# Motor_Interface_-_Pre-Charge_Logic.net
KiCad netlist of a schematic drawn in Altium Designer
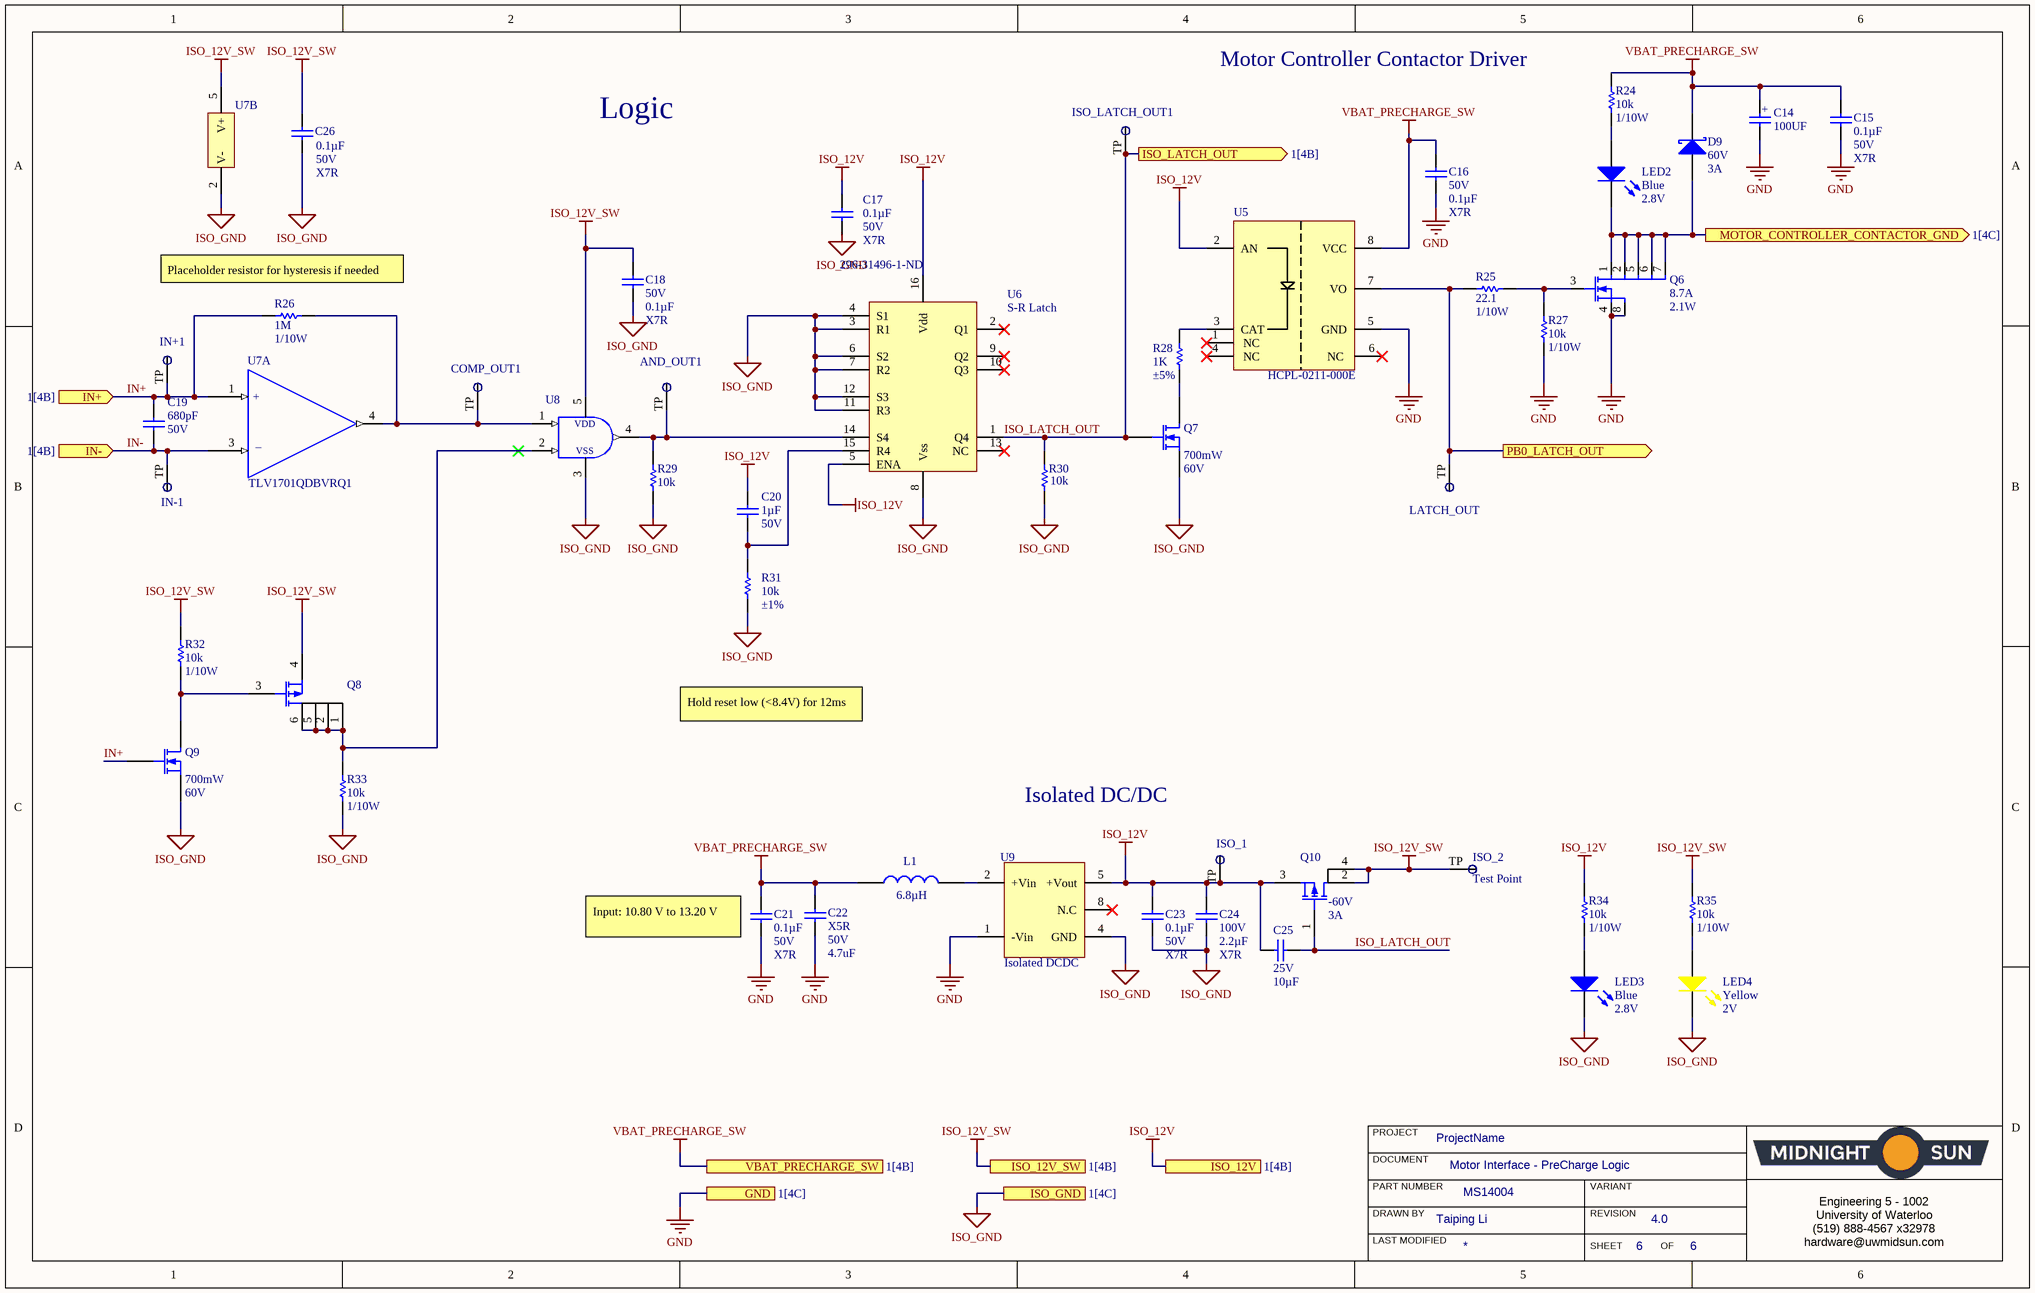
[diagram p0: Motor Interface - Pre-Charge Logic.SchDoc]

(export (version "E")
  (design (tool "Eeschema 10.0.6"))
  (components
    (comp (ref "AND_OUT1")
      (value "Test Point")
      (footprint "Test Point")
      (libsource (lib "Schematic Diagrams") (part "Test Point"))
    )
    (comp (ref "C14")
      (value "100UF")
      (footprint "CAP ALUM 6.3MM RADIAL SMD")
      (description "100µF 35V Aluminum Electrolytic Capacitors Radial, Can - SMD 2000 Hrs @ 85°C")
      (fields (field (name "TOLERANCE") "20%") (field (name "VOLTAGE") "35V"))
      (libsource (lib "altium-import") (part "root_0_CAP ALUM 100UF 20% 35V SMD_"))
    )
    (comp (ref "C15")
      (value "CAP CER 0.1UF 50V 10% X7R 0603")
      (footprint "CAP, 0603")
      (description "0.10µF ±10% 50V Ceramic Capacitor X7R 0603 (1608 Metric)")
      (fields
        (field (name "TOLERANCE") "±10%")
        (field (name "CAPACITANCE") "0.1µF")
        (field (name "VOLTAGE") "50V")
        (field (name "TEMPERATURE COEFFICIENT") "X7R")
      )
      (libsource (lib "Schematic Diagrams") (part "CAP CER 0.1UF 50V 10% X7R 0603"))
    )
    (comp (ref "C16")
      (value "CAP CER 0.1UF 50V 10% X7R 0603")
      (footprint "CAP, 0603")
      (description "0.10µF ±10% 50V Ceramic Capacitor X7R 0603 (1608 Metric)")
      (fields
        (field (name "VOLTAGE") "50V")
        (field (name "TOLERANCE") "±10%")
        (field (name "CAPACITANCE") "0.1µF")
        (field (name "TEMPERATURE COEFFICIENT") "X7R")
      )
      (libsource (lib "Schematic Diagrams") (part "CAP CER 0.1UF 50V 10% X7R 0603"))
    )
    (comp (ref "C17")
      (value "CAP CER 0.1UF 50V 10% X7R 0603")
      (footprint "CAP, 0603")
      (description "0.10µF ±10% 50V Ceramic Capacitor X7R 0603 (1608 Metric)")
      (fields
        (field (name "VOLTAGE") "50V")
        (field (name "TOLERANCE") "±10%")
        (field (name "CAPACITANCE") "0.1µF")
        (field (name "TEMPERATURE COEFFICIENT") "X7R")
      )
      (libsource (lib "Schematic Diagrams") (part "CAP CER 0.1UF 50V 10% X7R 0603"))
    )
    (comp (ref "C18")
      (value "CAP CER 0.1UF 50V 10% X7R 0603")
      (footprint "CAP, 0603")
      (description "0.10µF ±10% 50V Ceramic Capacitor X7R 0603 (1608 Metric)")
      (fields
        (field (name "VOLTAGE") "50V")
        (field (name "TOLERANCE") "±10%")
        (field (name "CAPACITANCE") "0.1µF")
        (field (name "TEMPERATURE COEFFICIENT") "X7R")
      )
      (libsource (lib "Schematic Diagrams") (part "CAP CER 0.1UF 50V 10% X7R 0603"))
    )
    (comp (ref "C19")
      (value "CAP CER 680PF 50V C0G/NP0 0603")
      (footprint "CAP, 0603")
      (description "680pF ±5% 50V Ceramic Capacitor C0G, NP0 0603 (1608 Metric)")
      (fields
        (field (name "MANUFACTURER") "Samsung")
        (field (name "MANUFACTURER PART NUMBER") "CL10C681JB8NNNC")
        (field (name "VOLTAGE") "50V")
        (field (name "CAPACITANCE") "680pF")
      )
      (libsource (lib "Schematic Diagrams") (part "CAP CER 680PF 50V C0G 0603"))
    )
    (comp (ref "C20")
      (value "CAP CER 1UF 50V 10% X7R 0603")
      (footprint "CAP, 0603")
      (description "1µF ±10% 50V Ceramic Capacitor X7R 0603 (1608 Metric)")
      (fields
        (field (name "VOLTAGE") "50V")
        (field (name "TOLERANCE") "±10%")
        (field (name "CAPACITANCE") "1µF")
      )
      (libsource (lib "Schematic Diagrams") (part "CAP CER 1UF 50V 10% X7R 0603"))
    )
    (comp (ref "C21")
      (value "CAP CER 0.1UF 50V 10% X7R 0603")
      (footprint "CAP, 0603")
      (description "0.10µF ±10% 50V Ceramic Capacitor X7R 0603 (1608 Metric)")
      (fields
        (field (name "TOLERANCE") "±10%")
        (field (name "CAPACITANCE") "0.1µF")
        (field (name "VOLTAGE") "50V")
        (field (name "TEMPERATURE COEFFICIENT") "X7R")
      )
      (libsource (lib "altium-import") (part "root_0_CAP CER 0.1UF 50V 10% X7R 0603_"))
    )
    (comp (ref "C22")
      (value "4.7uF")
      (footprint "CAP, 0805")
      (description "4.7µF ±20% 50V Ceramic Capacitor X5R 0805 (2012 Metric)")
      (fields
        (field (name "TOLERANCE") "±20%")
        (field (name "TEMPERATURE COEFFICIENT") "X5R")
        (field (name "VOLTAGE - RATED") "50V")
        (field (name "Comment") "CAP CER 4.7UF 50V 10% X5R 0805")
      )
      (libsource (lib "Schematic Diagrams") (part "CAP CER 4.7UF 50V 10% X5R 0805"))
    )
    (comp (ref "C23")
      (value "CAP CER 0.1UF 50V 10% X7R 0603")
      (footprint "CAP, 0603")
      (description "0.10µF ±10% 50V Ceramic Capacitor X7R 0603 (1608 Metric)")
      (fields
        (field (name "TOLERANCE") "±10%")
        (field (name "CAPACITANCE") "0.1µF")
        (field (name "VOLTAGE") "50V")
        (field (name "TEMPERATURE COEFFICIENT") "X7R")
      )
      (libsource (lib "altium-import") (part "root_0_CAP CER 0.1UF 50V 10% X7R 0603_"))
    )
    (comp (ref "C24")
      (value "CAP CER 2.2UF 100V ±20% X7R 1206")
      (footprint "CAP, 1206")
      (description "2.2µF ±20% 100V Ceramic Capacitor X7R 1206 (3216 Metric)")
      (fields
        (field (name "VOLTAGE") "100V")
        (field (name "TOLERANCE") "±20%")
        (field (name "CAPACITANCE") "2.2µF")
        (field (name "TEMPERATURE COEFFICIENT") "X7R")
      )
      (libsource (lib "Schematic Diagrams") (part "CAP CER 2.2UF 100V ±20% X7R 1206"))
    )
    (comp (ref "C25")
      (value "CAP CER 10uF 25V 10% X5R 0805")
      (footprint "CAP, 0805")
      (description "10µF ±10% 25V Ceramic Capacitor X5R 0805 (2012 Metric)")
      (fields
        (field (name "MANUFACTURER") "Murata Electronics North America")
        (field (name "MANUFACTURER PART NUMBER") "GRM21BR61E106KA73L")
        (field (name "VOLTAGE - RATED") "25V")
        (field (name "CAPACITANCE") "10µF")
      )
      (libsource (lib "Schematic Diagrams") (part "CAP CER 10uF 25V 10% X5R 0805"))
    )
    (comp (ref "C26")
      (value "CAP CER 0.1UF 50V 10% X7R 0603")
      (footprint "CAP, 0603")
      (description "0.10µF ±10% 50V Ceramic Capacitor X7R 0603 (1608 Metric)")
      (fields
        (field (name "VOLTAGE") "50V")
        (field (name "TOLERANCE") "±10%")
        (field (name "CAPACITANCE") "0.1µF")
        (field (name "TEMPERATURE COEFFICIENT") "X7R")
      )
      (libsource (lib "Schematic Diagrams") (part "CAP CER 0.1UF 50V 10% X7R 0603"))
    )
    (comp (ref "COMP_OUT1")
      (value "Test Point")
      (footprint "Test Point")
      (libsource (lib "Schematic Diagrams") (part "Test Point"))
    )
    (comp (ref "D9")
      (value "DIODE SCHOTTKY 60V 3A SMA")
      (footprint "Diode, SMA")
      (description "Diode Schottky 60V 3A Surface Mount SMA")
      (fields
        (field (name "VOLTAGE - DC REVERSE (VR) (MAX)") "60V")
        (field (name "CURRENT - AVERAGE RECTIFIED (IO)") "3A")
      )
      (libsource (lib "Schematic Diagrams") (part "DIODE SCHOTTKY 60V 3A SMA"))
    )
    (comp (ref "IN+1")
      (value "Test Point")
      (footprint "Test Point")
      (libsource (lib "Schematic Diagrams") (part "Test Point"))
    )
    (comp (ref "IN-1")
      (value "Test Point")
      (footprint "Test Point")
      (libsource (lib "Schematic Diagrams") (part "Test Point"))
    )
    (comp (ref "ISO_1")
      (value "Test Point")
      (footprint "Test Point")
      (libsource (lib "Schematic Diagrams") (part "Test Point"))
    )
    (comp (ref "ISO_2")
      (value "Test Point")
      (footprint "Test Point")
      (libsource (lib "Schematic Diagrams") (part "Test Point"))
    )
    (comp (ref "ISO_LATCH_OUT1")
      (value "Test Point")
      (footprint "Test Point")
      (libsource (lib "Schematic Diagrams") (part "Test Point"))
    )
    (comp (ref "L1")
      (value "IND 6.8uH 260mA 20% 1210")
      (footprint "NLFV32T-6R8M-EF/IND 6.8uH")
      (description "6.8µH Shielded Wirewound Inductor 260mA 204 mOhm Max 1210 (3225 Metric)")
      (fields (field (name "TOLERANCE") "±20%") (field (name "INDUCTANCE") "6.8µH"))
      (libsource (lib "Schematic Diagrams") (part "IND 6.8uH 260mA 20% 1210"))
    )
    (comp (ref "LATCH_OUT")
      (value "Test Point")
      (footprint "Test Point")
      (libsource (lib "Schematic Diagrams") (part "Test Point"))
    )
    (comp (ref "LED2")
      (value "LED BLUE CLEAR 2.8V 0603")
      (footprint "LED_0603")
      (description "Blue 470nm LED Indication - Discrete 2.8V 0603 (1608 Metric)")
      (fields (field (name "COLOR") "Blue") (field (name "VOLTAGE - FORWARD (VF) (TYP)") "2.8V"))
      (libsource (lib "altium-import") (part "root_3_LED BLUE CLEAR 2.8V 0603_"))
    )
    (comp (ref "LED3")
      (value "LED BLUE CLEAR 2.8V 0603")
      (footprint "LED_0603")
      (description "Blue 470nm LED Indication - Discrete 2.8V 0603 (1608 Metric)")
      (fields (field (name "COLOR") "Blue") (field (name "VOLTAGE - FORWARD (VF) (TYP)") "2.8V"))
      (libsource (lib "Schematic Diagrams") (part "LED BLUE CLEAR 2.8V 0603"))
    )
    (comp (ref "LED4")
      (value "LED YELLOW CLEAR 2.1V 0603")
      (footprint "LED_0603")
      (description "Yellow 590nm LED Indication - Discrete 2V 0603 (1608 Metric)")
      (fields
        (field (name "MANUFACTURER") "Wurth Electronics Inc.")
        (field (name "MANUFACTURER PART NUMBER") "150060YS75000")
        (field (name "COLOR") "Yellow")
        (field (name "VOLTAGE - FORWARD (VF) (TYP)") "2V")
      )
      (libsource (lib "Schematic Diagrams") (part "LED YELLOW CLEAR 2.1V 0603"))
    )
    (comp (ref "Q6")
      (value "MOSFET N-CH 30V 8.7A 2.1W 6-PQFN (2x2)")
      (footprint "MOSFET N-CH 30V 12A 2mmx2mm PQFN")
      (fields
        (field (name "CURRENT - CONTINUOUS DRAIN (ID) @ 25°C") "8.7A")
        (field (name "POWER DISSIPATION (MAX)") "2.1W")
      )
      (libsource (lib "altium-import") (part "root_0_MOSFET N-CH 30V 8.7A 2.1W 6-PQFN (2x2)_"))
    )
    (comp (ref "Q7")
      (value "MOSFET N-CH 60V 310MA SOT23")
      (footprint "SOT23")
      (description "N-Channel 60V 310mA (Ta) 370mW (Ta) Surface Mount SOT-23")
      (fields
        (field (name "MANUFACTURER") "Diodes")
        (field (name "MANUFACTURER PART NUMBER") "DMN6140L-7")
        (field (name "MAX POWER DISSIPATION") "700mW")
        (field (name "DRAIN TO SOURCE VOLTAGE (VDSS)") "60V")
      )
      (libsource (lib "Schematic Diagrams") (part "MOSFET N-CH 60V 310MA SOT23"))
    )
    (comp (ref "Q8")
      (value "MOSFET P-CH 30V 4A 1.6W SOT-23-6")
      (footprint "P-MOSFET")
      (description "P-Channel 30V 4A (Ta) 1.6W (Ta) Surface Mount SOT-23-6")
      (libsource (lib "Schematic Diagrams") (part "MOSFET P-CH 30V 4A 1.6W SOT-23-6"))
    )
    (comp (ref "Q9")
      (value "MOSFET N-CH 60V 310MA SOT23")
      (footprint "SOT23")
      (description "N-Channel 60V 310mA (Ta) 370mW (Ta) Surface Mount SOT-23")
      (fields
        (field (name "MANUFACTURER") "Diodes")
        (field (name "MANUFACTURER PART NUMBER") "DMN6140L-7")
        (field (name "MAX POWER DISSIPATION") "700mW")
        (field (name "DRAIN TO SOURCE VOLTAGE (VDSS)") "60V")
      )
      (libsource (lib "Schematic Diagrams") (part "MOSFET N-CH 60V 310MA SOT23"))
    )
    (comp (ref "Q10")
      (value "P-Channel")
      (footprint "SOT223_N")
      (description "P-Channel 60V 3A (Ta) 2W (Ta) Surface Mount SOT-223")
      (fields
        (field (name "MANUFACTURER") "Diodes")
        (field (name "MANUFACTURER PART NUMBER") "ZXMP6A17GQTA")
        (field (name "CONTINUOUS DRAIN CURRENT (ID)") "3A")
        (field (name "DRAIN TO SOURCE BREAKDOWN VOLTAGE") "-60V")
      )
      (libsource (lib "Schematic Diagrams") (part "MOSFET P-CH 60V 3A SOT223"))
    )
    (comp (ref "R24")
      (value "RES 10K OHM 1% 1/10W 0603")
      (footprint "RES, 0603")
      (description "RES SMD 10K OHM 1% 1/10W 0603")
      (fields
        (field (name "TOLERANCE") "±1%")
        (field (name "RESISTANCE") "10k")
        (field (name "POWER") "1/10W")
      )
      (libsource (lib "Schematic Diagrams") (part "RES 10K OHM 1% 1/10W 0603"))
    )
    (comp (ref "R25")
      (value "RES 22.1 OHM 1% 1/10W 0603")
      (footprint "RES, 0603")
      (description "22.1 Ohm ±1% 0.1W, 1/10W Chip Resistor 0603 (1608 Metric) Moisture Resistant Thick Film")
      (fields
        (field (name "TOLERANCE") "±1%")
        (field (name "RESISTANCE") "22.1")
        (field (name "POWER") "1/10W")
      )
      (libsource (lib "Schematic Diagrams") (part "RES 22.1 OHM 1% 1/10W 0603"))
    )
    (comp (ref "R26")
      (value "RES 1M OHM 1% 1/10W 0603")
      (footprint "RES, 0603")
      (description "1M Ohm ±1% 0.1W, 1/10W Chip Resistor 0603 (1608 Metric) Moisture Resistant Thick Film")
      (fields
        (field (name "TOLERANCE") "±1%")
        (field (name "RESISTANCE (OHMS)") "1M")
        (field (name "POWER (WATTS)") "1/10W")
      )
      (libsource (lib "Schematic Diagrams") (part "RES 1M OHM 1% 1/10W 0603"))
    )
    (comp (ref "R27")
      (value "RES 10K OHM 1% 1/10W 0603")
      (footprint "RES, 0603")
      (description "RES SMD 10K OHM 1% 1/10W 0603")
      (fields
        (field (name "TOLERANCE") "±1%")
        (field (name "RESISTANCE") "10k")
        (field (name "POWER") "1/10W")
      )
      (libsource (lib "Schematic Diagrams") (part "RES 10K OHM 1% 1/10W 0603"))
    )
    (comp (ref "R28")
      (value "1K")
      (footprint "RES, 0603")
      (description "1k Ohm ±5% 0.1W, 1/10W Chip Resistor 0603 (1608 Metric)")
      (fields
        (field (name "MANUFACTURER") "Yageo")
        (field (name "MANUFACTURER PART NUMBER") "RC0603JR-071KL")
        (field (name "TOLERANCE") "±5%")
      )
      (libsource (lib "Schematic Diagrams") (part "RES 1K OHM 5% 1/10W 0603"))
    )
    (comp (ref "R29")
      (value "RES 10K OHM 1% 1/10W 0603")
      (footprint "RES, 0603")
      (description "RES SMD 10K OHM 1% 1/10W 0603")
      (fields
        (field (name "TOLERANCE") "±1%")
        (field (name "POWER") "1/10W")
        (field (name "RESISTANCE") "10k")
      )
      (libsource (lib "Schematic Diagrams") (part "RES 10K OHM 1% 1/10W 0603"))
    )
    (comp (ref "R30")
      (value "RES 10K OHM 1% 1/10W 0603")
      (footprint "RES, 0603")
      (description "RES SMD 10K OHM 1% 1/10W 0603")
      (fields
        (field (name "POWER") "1/10W")
        (field (name "TOLERANCE") "±1%")
        (field (name "RESISTANCE") "10k")
      )
      (libsource (lib "Schematic Diagrams") (part "RES 10K OHM 1% 1/10W 0603"))
    )
    (comp (ref "R31")
      (value "RES 10K OHM 1% 1/10W 0603")
      (footprint "RES, 0603")
      (description "RES SMD 10K OHM 1% 1/10W 0603")
      (fields
        (field (name "TOLERANCE") "±1%")
        (field (name "POWER") "1/10W")
        (field (name "RESISTANCE") "10k")
      )
      (libsource (lib "Schematic Diagrams") (part "RES 10K OHM 1% 1/10W 0603"))
    )
    (comp (ref "R32")
      (value "RES 10K OHM 1% 1/10W 0603")
      (footprint "RES, 0603")
      (description "RES SMD 10K OHM 1% 1/10W 0603")
      (fields
        (field (name "TOLERANCE") "±1%")
        (field (name "RESISTANCE") "10k")
        (field (name "POWER") "1/10W")
      )
      (libsource (lib "Schematic Diagrams") (part "RES 10K OHM 1% 1/10W 0603"))
    )
    (comp (ref "R33")
      (value "RES 10K OHM 1% 1/10W 0603")
      (footprint "RES, 0603")
      (description "RES SMD 10K OHM 1% 1/10W 0603")
      (fields
        (field (name "TOLERANCE") "±1%")
        (field (name "RESISTANCE") "10k")
        (field (name "POWER") "1/10W")
      )
      (libsource (lib "Schematic Diagrams") (part "RES 10K OHM 1% 1/10W 0603"))
    )
    (comp (ref "R34")
      (value "RES 10K OHM 1% 1/10W 0603")
      (footprint "RES, 0603")
      (description "RES SMD 10K OHM 1% 1/10W 0603")
      (fields
        (field (name "TOLERANCE") "±1%")
        (field (name "RESISTANCE") "10k")
        (field (name "POWER") "1/10W")
      )
      (libsource (lib "Schematic Diagrams") (part "RES 10K OHM 1% 1/10W 0603"))
    )
    (comp (ref "R35")
      (value "RES 10K OHM 1% 1/10W 0603")
      (footprint "RES, 0603")
      (description "RES SMD 10K OHM 1% 1/10W 0603")
      (fields
        (field (name "TOLERANCE") "±1%")
        (field (name "RESISTANCE") "10k")
        (field (name "POWER") "1/10W")
      )
      (libsource (lib "Schematic Diagrams") (part "RES 10K OHM 1% 1/10W 0603"))
    )
    (comp (ref "U5")
      (value "IC OPTOISOLATOR 3.75KV PUSH PULL 8-SOIC")
      (footprint "IC OPTOISOLATOR HCPL-0211 SO-8")
      (fields
        (field (name "MANUFACTURER") "Broadcom Avago")
        (field (name "MANUFACTURER PART NUMBER") "HCPL-0211-000E")
      )
      (libsource (lib "Schematic Diagrams") (part "IC OPTOISOLATOR 3.75KV PUSH PULL 8-SOIC"))
    )
    (comp (ref "U6")
      (value "IC SR LATCH 4CH 16SOIC")
      (footprint "IC, SR Latch, CD4043BDR")
      (description "S-R Latch 4 Channel 1:1 IC Tri-State 16-TSSOP")
      (fields
        (field (name "SUPPLIER PART NUMBER 1") "296-31496-1-ND")
        (field (name "LOGIC TYPE") "S-R Latch")
      )
      (libsource (lib "Schematic Diagrams") (part "IC SR LATCH 4CH 16SOIC"))
    )
    (comp (ref "U7")
      (value "IC COMPARATOR TLV1701 SOT-23-5")
      (footprint "SOT95P280X145-5N")
      (description "Comparator General Purpose Open Collector SOT-23-5")
      (fields
        (field (name "MANUFACTURER") "Texas Instruments")
        (field (name "MANUFACTURER PART NUMBER") "TLV1701QDBVRQ1")
      )
      (libsource (lib "Schematic Diagrams") (part "IC COMPARATOR TLV1701 SOT-23-5"))
    )
    (comp (ref "U8")
      (value "IC AND GATE 1CH 5-SSOP")
      (footprint "IC, 2-Input AND Gate")
      (description "AND Gate IC 1 Channel 5-SSOP")
      (libsource (lib "Schematic Diagrams") (part "IC AND GATE 1CH 5-SSOP"))
    )
    (comp (ref "U9")
      (value "IC DCDC ISOLATED 12V 1W 8-SMD 5-LEAD")
      (footprint "IC, Isolated DCDC")
      (description "Isolated Module DC DC Converter 1 Output 12V 84mA 10.8V - 13.2V Input")
      (fields (field (name "POWER") "1W") (field (name "TYPE") "Isolated DCDC"))
      (libsource (lib "Schematic Diagrams") (part "IC DCDC ISOLATED 12V 1W 8-SMD 5-LEAD"))
    )
  )
  (nets
    (net (code "1") (name "/IN+") (class "Default")
      (node (ref "C19") (pin "1") (pinfunction "1_1") (pintype "passive"))
      (node (ref "IN+1") (pin "TP") (pinfunction "1_TP") (pintype "passive"))
      (node (ref "Q9") (pin "3") (pinfunction "G_3") (pintype "passive"))
      (node (ref "R26") (pin "1") (pinfunction "1_1") (pintype "passive"))
      (node (ref "U7") (pin "1") (pinfunction "+IN_1") (pintype "input"))
    )
    (net (code "2") (name "/IN-") (class "Default")
      (node (ref "C19") (pin "2") (pinfunction "2_2") (pintype "passive"))
      (node (ref "IN-1") (pin "TP") (pinfunction "1_TP") (pintype "passive"))
      (node (ref "U7") (pin "3") (pinfunction "-IN_3") (pintype "input"))
    )
    (net (code "3") (name "/ISO_LATCH_OUT") (class "Default")
      (node (ref "C25") (pin "2") (pinfunction "2_2") (pintype "passive"))
      (node (ref "ISO_LATCH_OUT1") (pin "TP") (pinfunction "1_TP") (pintype "passive"))
      (node (ref "Q10") (pin "1") (pinfunction "G_1") (pintype "passive"))
      (node (ref "Q7") (pin "3") (pinfunction "G_3") (pintype "passive"))
      (node (ref "R30") (pin "2") (pinfunction "2_2") (pintype "passive"))
      (node (ref "U6") (pin "1") (pinfunction "Q4_1") (pintype "passive"))
    )
    (net (code "4") (name "/MOTOR_CONTROLLER_CONTACTOR_GND") (class "Default")
      (node (ref "D9") (pin "1") (pinfunction "1_1") (pintype "passive"))
      (node (ref "LED2") (pin "2") (pinfunction "K_2") (pintype "passive"))
      (node (ref "Q6") (pin "1") (pinfunction "D_1") (pintype "passive"))
      (node (ref "Q6") (pin "2") (pinfunction "D_2") (pintype "passive"))
      (node (ref "Q6") (pin "5") (pinfunction "D_5") (pintype "passive"))
      (node (ref "Q6") (pin "6") (pinfunction "D_6") (pintype "passive"))
      (node (ref "Q6") (pin "7") (pinfunction "D_7") (pintype "passive"))
    )
    (net (code "5") (name "/PB0_LATCH_OUT") (class "Default")
      (node (ref "LATCH_OUT") (pin "TP") (pinfunction "1_TP") (pintype "passive"))
      (node (ref "R25") (pin "1") (pinfunction "1_1") (pintype "passive"))
      (node (ref "U5") (pin "7") (pinfunction "VO_7") (pintype "passive"))
    )
    (net (code "6") (name "GND") (class "Default")
      (node (ref "C14") (pin "2") (pinfunction "2_2") (pintype "passive"))
      (node (ref "C15") (pin "2") (pinfunction "2_2") (pintype "passive"))
      (node (ref "C16") (pin "2") (pinfunction "2_2") (pintype "passive"))
      (node (ref "C21") (pin "2") (pinfunction "2_2") (pintype "passive"))
      (node (ref "C22") (pin "1") (pinfunction "1_1") (pintype "passive"))
      (node (ref "Q6") (pin "4") (pinfunction "S_4") (pintype "passive"))
      (node (ref "Q6") (pin "8") (pinfunction "S_8") (pintype "passive"))
      (node (ref "R27") (pin "2") (pinfunction "2_2") (pintype "passive"))
      (node (ref "U5") (pin "5") (pinfunction "GND_5") (pintype "passive"))
      (node (ref "U9") (pin "1") (pinfunction "-Vin_1") (pintype "passive"))
    )
    (net (code "7") (name "ISO_12V") (class "Default")
      (node (ref "C17") (pin "2") (pinfunction "2_2") (pintype "passive"))
      (node (ref "C20") (pin "1") (pinfunction "1_1") (pintype "passive"))
      (node (ref "C23") (pin "1") (pinfunction "1_1") (pintype "passive"))
      (node (ref "C24") (pin "2") (pinfunction "2_2") (pintype "passive"))
      (node (ref "C25") (pin "1") (pinfunction "1_1") (pintype "passive"))
      (node (ref "ISO_1") (pin "TP") (pinfunction "1_TP") (pintype "passive"))
      (node (ref "Q10") (pin "3") (pinfunction "S_3") (pintype "passive"))
      (node (ref "R34") (pin "2") (pinfunction "2_2") (pintype "passive"))
      (node (ref "U5") (pin "2") (pinfunction "AN_2") (pintype "passive"))
      (node (ref "U6") (pin "16") (pinfunction "Vdd_16") (pintype "passive"))
      (node (ref "U6") (pin "5") (pinfunction "ENA_5") (pintype "passive"))
      (node (ref "U9") (pin "5") (pinfunction "+Vout_5") (pintype "passive"))
    )
    (net (code "8") (name "ISO_12V_SW") (class "Default")
      (node (ref "C18") (pin "2") (pinfunction "2_2") (pintype "passive"))
      (node (ref "C26") (pin "2") (pinfunction "2_2") (pintype "passive"))
      (node (ref "ISO_2") (pin "TP") (pinfunction "1_TP") (pintype "passive"))
      (node (ref "Q10") (pin "2") (pinfunction "D_2") (pintype "passive"))
      (node (ref "Q10") (pin "4") (pinfunction "D_4") (pintype "passive"))
      (node (ref "Q8") (pin "4") (pinfunction "S_4") (pintype "passive"))
      (node (ref "R32") (pin "1") (pinfunction "1_1") (pintype "passive"))
      (node (ref "R35") (pin "2") (pinfunction "2_2") (pintype "passive"))
      (node (ref "U7") (pin "5") (pinfunction "V+_5") (pintype "power_in"))
      (node (ref "U8") (pin "5") (pinfunction "VCC_5") (pintype "power_in"))
    )
    (net (code "9") (name "ISO_GND") (class "Default")
      (node (ref "C17") (pin "1") (pinfunction "1_1") (pintype "passive"))
      (node (ref "C18") (pin "1") (pinfunction "1_1") (pintype "passive"))
      (node (ref "C23") (pin "2") (pinfunction "2_2") (pintype "passive"))
      (node (ref "C24") (pin "1") (pinfunction "1_1") (pintype "passive"))
      (node (ref "C26") (pin "1") (pinfunction "1_1") (pintype "passive"))
      (node (ref "LED3") (pin "2") (pinfunction "K_2") (pintype "passive"))
      (node (ref "LED4") (pin "2") (pinfunction "K_2") (pintype "passive"))
      (node (ref "Q7") (pin "2") (pinfunction "S_2") (pintype "passive"))
      (node (ref "Q9") (pin "2") (pinfunction "S_2") (pintype "passive"))
      (node (ref "R29") (pin "1") (pinfunction "1_1") (pintype "passive"))
      (node (ref "R30") (pin "1") (pinfunction "1_1") (pintype "passive"))
      (node (ref "R31") (pin "2") (pinfunction "2_2") (pintype "passive"))
      (node (ref "R33") (pin "2") (pinfunction "2_2") (pintype "passive"))
      (node (ref "U6") (pin "11") (pinfunction "R3_11") (pintype "passive"))
      (node (ref "U6") (pin "12") (pinfunction "S3_12") (pintype "passive"))
      (node (ref "U6") (pin "3") (pinfunction "R1_3") (pintype "passive"))
      (node (ref "U6") (pin "4") (pinfunction "S1_4") (pintype "passive"))
      (node (ref "U6") (pin "6") (pinfunction "S2_6") (pintype "passive"))
      (node (ref "U6") (pin "7") (pinfunction "R2_7") (pintype "passive"))
      (node (ref "U6") (pin "8") (pinfunction "Vss_8") (pintype "passive"))
      (node (ref "U7") (pin "2") (pinfunction "V-_2") (pintype "power_in"))
      (node (ref "U8") (pin "3") (pinfunction "GND_3") (pintype "power_in"))
      (node (ref "U9") (pin "4") (pinfunction "GND_4") (pintype "passive"))
    )
    (net (code "10") (name "Net-(AND_OUT1-1)") (class "Default")
      (node (ref "AND_OUT1") (pin "TP") (pinfunction "1_TP") (pintype "passive"))
      (node (ref "R29") (pin "2") (pinfunction "2_2") (pintype "passive"))
      (node (ref "U6") (pin "14") (pinfunction "S4_14") (pintype "passive"))
      (node (ref "U8") (pin "4") (pinfunction "Y_4") (pintype "output"))
    )
    (net (code "11") (name "Net-(COMP_OUT1-1)") (class "Default")
      (node (ref "COMP_OUT1") (pin "TP") (pinfunction "1_TP") (pintype "passive"))
      (node (ref "R26") (pin "2") (pinfunction "2_2") (pintype "passive"))
      (node (ref "U7") (pin "4") (pinfunction "OUT_4") (pintype "output"))
      (node (ref "U8") (pin "1") (pinfunction "A_1") (pintype "input"))
    )
    (net (code "12") (name "Net-(LED2-A)") (class "Default")
      (node (ref "LED2") (pin "1") (pinfunction "A_1") (pintype "passive"))
      (node (ref "R24") (pin "1") (pinfunction "1_1") (pintype "passive"))
    )
    (net (code "13") (name "Net-(LED3-A)") (class "Default")
      (node (ref "LED3") (pin "1") (pinfunction "A_1") (pintype "passive"))
      (node (ref "R34") (pin "1") (pinfunction "1_1") (pintype "passive"))
    )
    (net (code "14") (name "Net-(LED4-A)") (class "Default")
      (node (ref "LED4") (pin "1") (pinfunction "A_1") (pintype "passive"))
      (node (ref "R35") (pin "1") (pinfunction "1_1") (pintype "passive"))
    )
    (net (code "15") (name "Net-(Q6-G)") (class "Default")
      (node (ref "Q6") (pin "3") (pinfunction "G_3") (pintype "passive"))
      (node (ref "R25") (pin "2") (pinfunction "2_2") (pintype "passive"))
      (node (ref "R27") (pin "1") (pinfunction "1_1") (pintype "passive"))
    )
    (net (code "16") (name "Net-(Q7-D)") (class "Default")
      (node (ref "Q7") (pin "1") (pinfunction "D_1") (pintype "passive"))
      (node (ref "R28") (pin "1") (pinfunction "1_1") (pintype "passive"))
    )
    (net (code "17") (name "Net-(Q8-G)") (class "Default")
      (node (ref "Q8") (pin "3") (pinfunction "G_3") (pintype "passive"))
      (node (ref "Q9") (pin "1") (pinfunction "D_1") (pintype "passive"))
      (node (ref "R32") (pin "2") (pinfunction "2_2") (pintype "passive"))
    )
    (net (code "18") (name "Net-(U5-CAT)") (class "Default")
      (node (ref "R28") (pin "2") (pinfunction "2_2") (pintype "passive"))
      (node (ref "U5") (pin "3") (pinfunction "CAT_3") (pintype "passive"))
    )
    (net (code "19") (name "Net-(U6-R4)") (class "Default")
      (node (ref "C20") (pin "2") (pinfunction "2_2") (pintype "passive"))
      (node (ref "R31") (pin "1") (pinfunction "1_1") (pintype "passive"))
      (node (ref "U6") (pin "15") (pinfunction "R4_15") (pintype "passive"))
    )
    (net (code "20") (name "Net-(U8-B)") (class "Default")
      (node (ref "Q8") (pin "1") (pinfunction "D_1") (pintype "passive"))
      (node (ref "Q8") (pin "2") (pinfunction "D_2") (pintype "passive"))
      (node (ref "Q8") (pin "5") (pinfunction "D_5") (pintype "passive"))
      (node (ref "Q8") (pin "6") (pinfunction "D_6") (pintype "passive"))
      (node (ref "R33") (pin "1") (pinfunction "1_1") (pintype "passive"))
      (node (ref "U8") (pin "2") (pinfunction "B_2") (pintype "input"))
    )
    (net (code "21") (name "Net-(U9-+Vin)") (class "Default")
      (node (ref "L1") (pin "2") (pinfunction "2_2") (pintype "passive"))
      (node (ref "U9") (pin "2") (pinfunction "+Vin_2") (pintype "passive"))
    )
    (net (code "22") (name "VBAT_PRECHARGE_SW") (class "Default")
      (node (ref "C14") (pin "1") (pinfunction "1_1") (pintype "passive"))
      (node (ref "C15") (pin "1") (pinfunction "1_1") (pintype "passive"))
      (node (ref "C16") (pin "1") (pinfunction "1_1") (pintype "passive"))
      (node (ref "C21") (pin "1") (pinfunction "1_1") (pintype "passive"))
      (node (ref "C22") (pin "2") (pinfunction "2_2") (pintype "passive"))
      (node (ref "D9") (pin "2") (pinfunction "2_2") (pintype "passive"))
      (node (ref "L1") (pin "1") (pinfunction "1_1") (pintype "passive"))
      (node (ref "R24") (pin "2") (pinfunction "2_2") (pintype "passive"))
      (node (ref "U5") (pin "8") (pinfunction "VCC_8") (pintype "passive"))
    )
    (net (code "23") (name "unconnected-(U5-NC-Pad1)") (class "Default")
      (node (ref "U5") (pin "1") (pinfunction "NC_1") (pintype "passive+no_connect"))
    )
    (net (code "24") (name "unconnected-(U5-NC-Pad4)") (class "Default")
      (node (ref "U5") (pin "4") (pinfunction "NC_4") (pintype "passive+no_connect"))
    )
    (net (code "25") (name "unconnected-(U5-NC-Pad6)") (class "Default")
      (node (ref "U5") (pin "6") (pinfunction "NC_6") (pintype "passive+no_connect"))
    )
    (net (code "26") (name "unconnected-(U6-NC-Pad13)") (class "Default")
      (node (ref "U6") (pin "13") (pinfunction "NC_13") (pintype "passive+no_connect"))
    )
    (net (code "27") (name "unconnected-(U6-Q1-Pad2)") (class "Default")
      (node (ref "U6") (pin "2") (pinfunction "Q1_2") (pintype "passive+no_connect"))
    )
    (net (code "28") (name "unconnected-(U6-Q2-Pad9)") (class "Default")
      (node (ref "U6") (pin "9") (pinfunction "Q2_9") (pintype "passive+no_connect"))
    )
    (net (code "29") (name "unconnected-(U6-Q3-Pad10)") (class "Default")
      (node (ref "U6") (pin "10") (pinfunction "Q3_10") (pintype "passive+no_connect"))
    )
    (net (code "30") (name "unconnected-(U9-N.C-Pad8)") (class "Default")
      (node (ref "U9") (pin "8") (pinfunction "N.C_8") (pintype "passive+no_connect"))
    )
  )
)
